# Bind-Board-V1-0.net
KiCad netlist of a schematic drawn in EAGLE
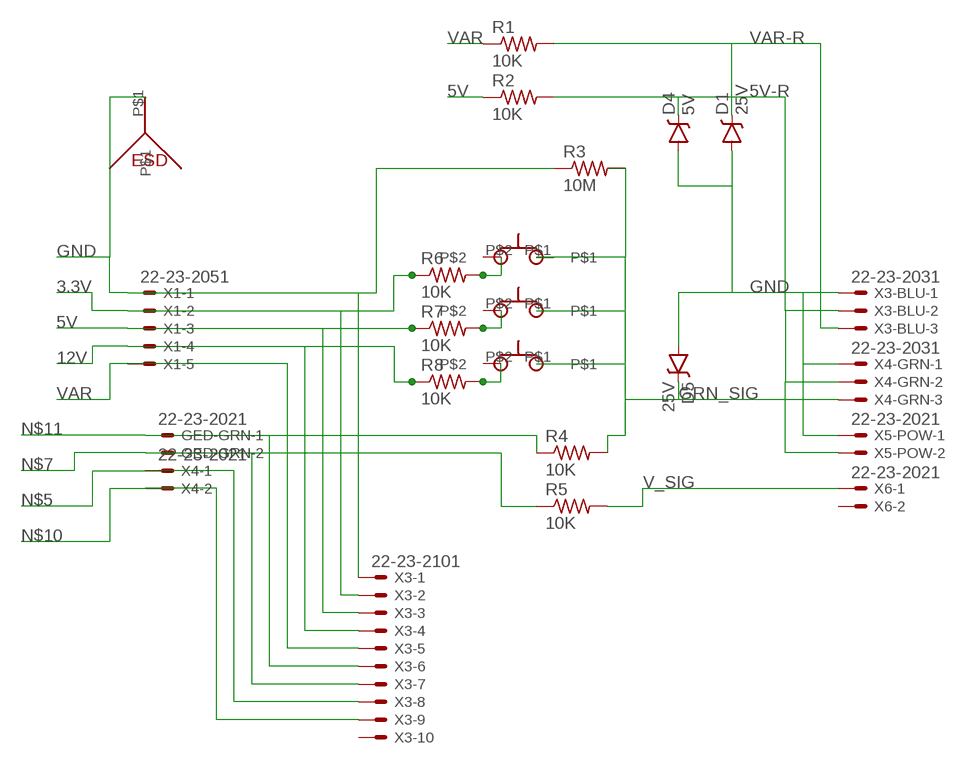
[diagram p0: schematic, sheet 1]

(export (version "E")
  (design (tool "Eeschema 10.0.6"))
  (components
    (comp (ref "D1")
      (value "25V")
      (footprint "eagle-import:SOT23-3")
      (libsource (lib "eagle-import") (part "ZLLS500ZLLS500"))
    )
    (comp (ref "D4")
      (value "5V")
      (footprint "eagle-import:SOT23-3")
      (libsource (lib "eagle-import") (part "ZLLS500ZLLS500"))
    )
    (comp (ref "D5")
      (value "25V")
      (footprint "eagle-import:SOT23-3")
      (libsource (lib "eagle-import") (part "ZLLS500ZLLS500"))
    )
    (comp (ref "GED-GRN")
      (value "22-23-2021")
      (footprint "eagle-import:22-23-2021")
      (fields (field (name "MF") "MOLEX"))
      (libsource (lib "eagle-import") (part "22-23-2021"))
    )
    (comp (ref "R1")
      (value "10K")
      (footprint "eagle-import:M2012")
      (libsource (lib "eagle-import") (part "R-US_M2012"))
    )
    (comp (ref "R2")
      (value "10K")
      (footprint "eagle-import:M2012")
      (libsource (lib "eagle-import") (part "R-US_M2012"))
    )
    (comp (ref "R3")
      (value "10M")
      (footprint "eagle-import:M2012")
      (libsource (lib "eagle-import") (part "R-US_M2012"))
    )
    (comp (ref "R4")
      (value "10K")
      (footprint "eagle-import:M2012")
      (libsource (lib "eagle-import") (part "R-US_M2012"))
    )
    (comp (ref "R5")
      (value "10K")
      (footprint "eagle-import:M2012")
      (libsource (lib "eagle-import") (part "R-US_M2012"))
    )
    (comp (ref "R6")
      (value "10K")
      (footprint "eagle-import:M2012")
      (libsource (lib "eagle-import") (part "R-US_M2012"))
    )
    (comp (ref "R7")
      (value "10K")
      (footprint "eagle-import:M2012")
      (libsource (lib "eagle-import") (part "R-US_M2012"))
    )
    (comp (ref "R8")
      (value "10K")
      (footprint "eagle-import:M2012")
      (libsource (lib "eagle-import") (part "R-US_M2012"))
    )
    (comp (ref "U$1")
      (value "PUSH-BUTTON-SWITCH")
      (footprint "eagle-import:PUSH-BUTTON-SWITCH")
      (libsource (lib "eagle-import") (part "PUSH-BUTTON-SWITCH"))
    )
    (comp (ref "U$2")
      (value "PUSH-BUTTON-SWITCH")
      (footprint "eagle-import:PUSH-BUTTON-SWITCH")
      (libsource (lib "eagle-import") (part "PUSH-BUTTON-SWITCH"))
    )
    (comp (ref "U$3")
      (value "PUSH-BUTTON-SWITCH")
      (footprint "eagle-import:PUSH-BUTTON-SWITCH")
      (libsource (lib "eagle-import") (part "PUSH-BUTTON-SWITCH"))
    )
    (comp (ref "U$4")
      (value "ESD-STAR")
      (footprint "eagle-import:ESD-STAR")
      (libsource (lib "eagle-import") (part "ESD-STAR"))
    )
    (comp (ref "X1")
      (value "22-23-2051")
      (footprint "eagle-import:22-23-2051")
      (fields (field (name "MF") "MOLEX"))
      (libsource (lib "eagle-import") (part "22-23-2051"))
    )
    (comp (ref "X3")
      (value "22-23-2101")
      (footprint "eagle-import:22-23-2101")
      (fields (field (name "MF") "MOLEX"))
      (libsource (lib "eagle-import") (part "22-23-2101"))
    )
    (comp (ref "X3-BLU")
      (value "22-23-2031")
      (footprint "eagle-import:22-23-2031")
      (fields (field (name "MF") "MOLEX"))
      (libsource (lib "eagle-import") (part "22-23-2031"))
    )
    (comp (ref "X4")
      (value "22-23-2021")
      (footprint "eagle-import:22-23-2021")
      (fields (field (name "MF") "MOLEX"))
      (libsource (lib "eagle-import") (part "22-23-2021"))
    )
    (comp (ref "X4-GRN")
      (value "22-23-2031")
      (footprint "eagle-import:22-23-2031")
      (fields (field (name "MF") "MOLEX"))
      (libsource (lib "eagle-import") (part "22-23-2031"))
    )
    (comp (ref "X5-POW")
      (value "22-23-2021")
      (footprint "eagle-import:22-23-2021")
      (fields (field (name "MF") "MOLEX"))
      (libsource (lib "eagle-import") (part "22-23-2021"))
    )
    (comp (ref "X6")
      (value "22-23-2021")
      (footprint "eagle-import:22-23-2021")
      (fields (field (name "MF") "MOLEX"))
      (libsource (lib "eagle-import") (part "22-23-2021"))
    )
  )
  (nets
    (net (code "1") (name "/3.3V") (class "Default")
      (node (ref "R6") (pin "1") (pinfunction "1_1") (pintype "passive"))
      (node (ref "X1") (pin "2") (pinfunction "S_2") (pintype "passive"))
      (node (ref "X3") (pin "2") (pinfunction "S_2") (pintype "passive"))
    )
    (net (code "2") (name "/5V") (class "Default")
      (node (ref "R2") (pin "1") (pinfunction "1_1") (pintype "passive"))
      (node (ref "R7") (pin "1") (pinfunction "1_1") (pintype "passive"))
      (node (ref "X1") (pin "3") (pinfunction "S_3") (pintype "passive"))
      (node (ref "X3") (pin "3") (pinfunction "S_3") (pintype "passive"))
    )
    (net (code "3") (name "/5V-R") (class "Default")
      (node (ref "D4") (pin "3") (pinfunction "C_3") (pintype "passive"))
      (node (ref "R2") (pin "2") (pinfunction "2_2") (pintype "passive"))
      (node (ref "X3-BLU") (pin "2") (pinfunction "S_2") (pintype "passive"))
      (node (ref "X4-GRN") (pin "2") (pinfunction "S_2") (pintype "passive"))
      (node (ref "X5-POW") (pin "2") (pinfunction "S_2") (pintype "passive"))
    )
    (net (code "4") (name "/12V") (class "Default")
      (node (ref "R8") (pin "1") (pinfunction "1_1") (pintype "passive"))
      (node (ref "X1") (pin "4") (pinfunction "S_4") (pintype "passive"))
      (node (ref "X3") (pin "4") (pinfunction "S_4") (pintype "passive"))
    )
    (net (code "5") (name "/GND") (class "Default")
      (node (ref "D1") (pin "1") (pinfunction "A_1") (pintype "passive"))
      (node (ref "D4") (pin "1") (pinfunction "A_1") (pintype "passive"))
      (node (ref "D5") (pin "1") (pinfunction "A_1") (pintype "passive"))
      (node (ref "R3") (pin "1") (pinfunction "1_1") (pintype "passive"))
      (node (ref "U$4") (pin "P$1") (pinfunction "P$1_P$1") (pintype "bidirectional"))
      (node (ref "X1") (pin "1") (pinfunction "S_1") (pintype "passive"))
      (node (ref "X3") (pin "1") (pinfunction "S_1") (pintype "passive"))
      (node (ref "X3-BLU") (pin "1") (pinfunction "S_1") (pintype "passive"))
      (node (ref "X4-GRN") (pin "1") (pinfunction "S_1") (pintype "passive"))
      (node (ref "X5-POW") (pin "1") (pinfunction "S_1") (pintype "passive"))
    )
    (net (code "6") (name "/GRN_SIG") (class "Default")
      (node (ref "D5") (pin "3") (pinfunction "C_3") (pintype "passive"))
      (node (ref "R3") (pin "2") (pinfunction "2_2") (pintype "passive"))
      (node (ref "R4") (pin "2") (pinfunction "2_2") (pintype "passive"))
      (node (ref "U$1") (pin "P$1") (pinfunction "P$1_P$1") (pintype "bidirectional"))
      (node (ref "U$2") (pin "P$1") (pinfunction "P$1_P$1") (pintype "bidirectional"))
      (node (ref "U$3") (pin "P$1") (pinfunction "P$1_P$1") (pintype "bidirectional"))
      (node (ref "X4-GRN") (pin "3") (pinfunction "S_3") (pintype "passive"))
    )
    (net (code "7") (name "/N$5") (class "Default")
      (node (ref "X3") (pin "8") (pinfunction "S_8") (pintype "passive"))
      (node (ref "X4") (pin "1") (pinfunction "S_1") (pintype "passive"))
    )
    (net (code "8") (name "/N$7") (class "Default")
      (node (ref "GED-GRN") (pin "2") (pinfunction "S_2") (pintype "passive"))
      (node (ref "R5") (pin "1") (pinfunction "1_1") (pintype "passive"))
      (node (ref "X3") (pin "7") (pinfunction "S_7") (pintype "passive"))
    )
    (net (code "9") (name "/N$10") (class "Default")
      (node (ref "X3") (pin "9") (pinfunction "S_9") (pintype "passive"))
      (node (ref "X4") (pin "2") (pinfunction "S_2") (pintype "passive"))
    )
    (net (code "10") (name "/N$11") (class "Default")
      (node (ref "GED-GRN") (pin "1") (pinfunction "S_1") (pintype "passive"))
      (node (ref "R4") (pin "1") (pinfunction "1_1") (pintype "passive"))
      (node (ref "X3") (pin "6") (pinfunction "S_6") (pintype "passive"))
    )
    (net (code "11") (name "/VAR") (class "Default")
      (node (ref "R1") (pin "1") (pinfunction "1_1") (pintype "passive"))
      (node (ref "X1") (pin "5") (pinfunction "S_5") (pintype "passive"))
      (node (ref "X3") (pin "5") (pinfunction "S_5") (pintype "passive"))
    )
    (net (code "12") (name "/VAR-R") (class "Default")
      (node (ref "D1") (pin "3") (pinfunction "C_3") (pintype "passive"))
      (node (ref "R1") (pin "2") (pinfunction "2_2") (pintype "passive"))
      (node (ref "X3-BLU") (pin "3") (pinfunction "S_3") (pintype "passive"))
    )
    (net (code "13") (name "/V_SIG") (class "Default")
      (node (ref "R5") (pin "2") (pinfunction "2_2") (pintype "passive"))
      (node (ref "X6") (pin "1") (pinfunction "S_1") (pintype "passive"))
    )
    (net (code "14") (name "Net-(R6-Pad2)") (class "Default")
      (node (ref "R6") (pin "2") (pinfunction "2_2") (pintype "passive"))
      (node (ref "U$1") (pin "P$2") (pinfunction "P$2_P$2") (pintype "bidirectional"))
    )
    (net (code "15") (name "Net-(R7-Pad2)") (class "Default")
      (node (ref "R7") (pin "2") (pinfunction "2_2") (pintype "passive"))
      (node (ref "U$2") (pin "P$2") (pinfunction "P$2_P$2") (pintype "bidirectional"))
    )
    (net (code "16") (name "Net-(R8-Pad2)") (class "Default")
      (node (ref "R8") (pin "2") (pinfunction "2_2") (pintype "passive"))
      (node (ref "U$3") (pin "P$2") (pinfunction "P$2_P$2") (pintype "bidirectional"))
    )
    (net (code "17") (name "unconnected-(X3B-S-Pad10)") (class "Default")
      (node (ref "X3") (pin "10") (pinfunction "S_10") (pintype "passive"))
    )
    (net (code "18") (name "unconnected-(X6B-S-Pad2)") (class "Default")
      (node (ref "X6") (pin "2") (pinfunction "S_2") (pintype "passive"))
    )
  )
)
